# LCDTFT_FPC40P_SPI4_3_2INCH_RTP.net
KiCad netlist of a schematic drawn in Altium Designer
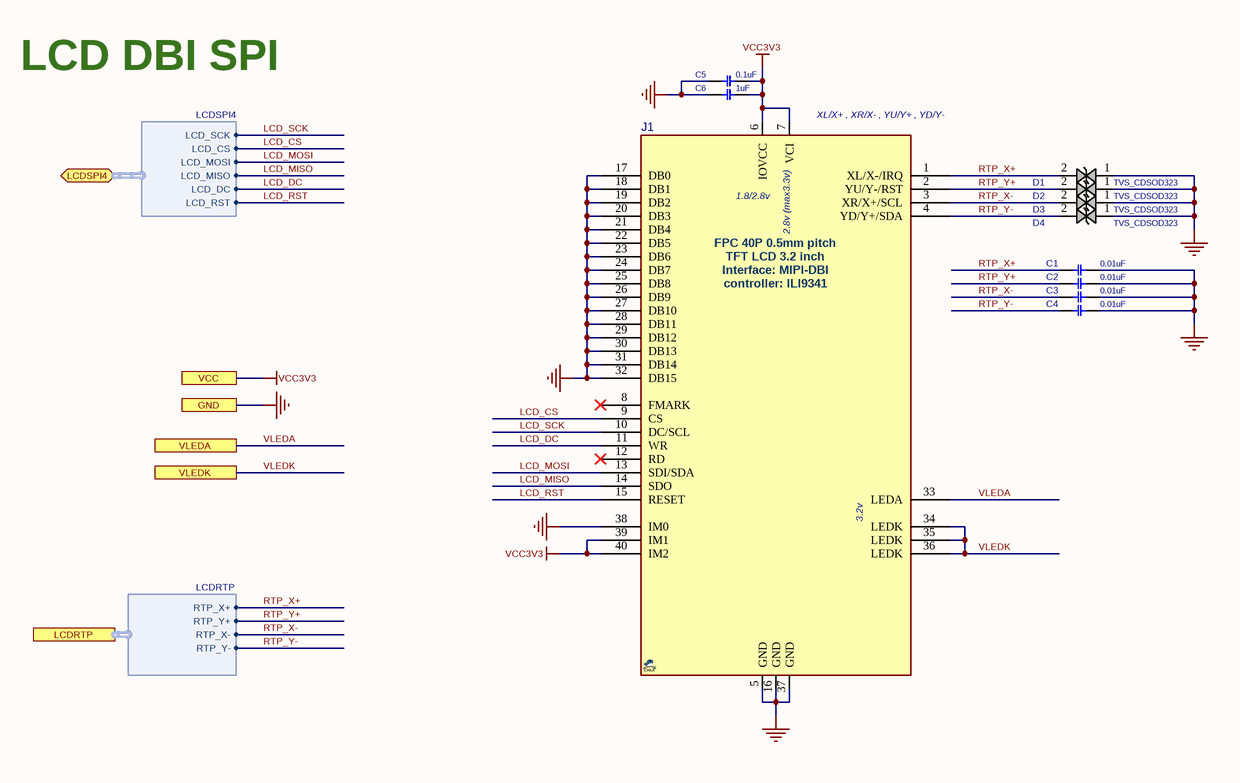
[diagram p0: LCDTFT_FPC40P_SPI4_3.2INCH_RTP.SchDoc]

(export (version "E")
  (design (tool "Eeschema 10.0.6"))
  (components
    (comp (ref "C1")
      (value "0.01uF")
      (footprint "C0402")
      (description "CAP, MLCC")
      (libsource (lib "passive_smd") (part "CAP_SMD_MLCC"))
    )
    (comp (ref "C2")
      (value "0.01uF")
      (footprint "C0402")
      (description "CAP, MLCC")
      (libsource (lib "passive_smd") (part "CAP_SMD_MLCC"))
    )
    (comp (ref "C3")
      (value "0.01uF")
      (footprint "C0402")
      (description "CAP, MLCC")
      (libsource (lib "passive_smd") (part "CAP_SMD_MLCC"))
    )
    (comp (ref "C4")
      (value "0.01uF")
      (footprint "C0402")
      (description "CAP, MLCC")
      (libsource (lib "passive_smd") (part "CAP_SMD_MLCC"))
    )
    (comp (ref "C5")
      (value "0.1uF")
      (footprint "C0402")
      (description "CAP, MLCC")
      (fields (field (name "MANF_P#") "GRM155R71H104KE14D") (field (name "MANF") "Murata"))
      (libsource (lib "passive_smd") (part "CAP_SMD_MLCC"))
    )
    (comp (ref "C6")
      (value "1uF")
      (footprint "C0402")
      (description "CAP, MLCC")
      (libsource (lib "passive_smd") (part "CAP_SMD_MLCC"))
    )
    (comp (ref "D1")
      (value "TVS_CDSOD323")
      (footprint "D0805")
      (description "TVS, ESD PROTECT, Bidirectional")
      (fields (field (name "MANF_P#") "CDSOD323-T12C") (field (name "MANF") "Bourns"))
      (libsource (lib "protect_tvs_esd_fuse") (part "TVS_CDSOD323"))
    )
    (comp (ref "D2")
      (value "TVS_CDSOD323")
      (footprint "D0805")
      (description "TVS, ESD PROTECT, Bidirectional")
      (fields (field (name "MANF_P#") "CDSOD323-T12C") (field (name "MANF") "Bourns"))
      (libsource (lib "protect_tvs_esd_fuse") (part "TVS_CDSOD323"))
    )
    (comp (ref "D3")
      (value "TVS_CDSOD323")
      (footprint "D0805")
      (description "TVS, ESD PROTECT, Bidirectional")
      (fields (field (name "MANF_P#") "CDSOD323-T12C") (field (name "MANF") "Bourns"))
      (libsource (lib "protect_tvs_esd_fuse") (part "TVS_CDSOD323"))
    )
    (comp (ref "D4")
      (value "TVS_CDSOD323")
      (footprint "D0805")
      (description "TVS, ESD PROTECT, Bidirectional")
      (fields (field (name "MANF_P#") "CDSOD323-T12C") (field (name "MANF") "Bourns"))
      (libsource (lib "protect_tvs_esd_fuse") (part "TVS_CDSOD323"))
    )
    (comp (ref "J1")
      (value "FPC50_40")
      (footprint "FPC50_40T")
      (description "LCD TFT Color, FPC40P, 3.2\" with touch")
      (fields (field (name "MANF") "Hirose") (field (name "MANF_P#") "FH12A-40S-0.5SH"))
      (libsource (lib "lcdtft") (part "LCDTFT_DBI_FPC40P_3.2INCH"))
    )
  )
  (nets
    (net (code "3") (name "/LCD_CS") (class "Default")
      (node (ref "J1") (pin "9") (pinfunction "CS_9") (pintype "passive"))
    )
    (net (code "4") (name "/LCD_DC") (class "Default")
      (node (ref "J1") (pin "11") (pinfunction "WR_11") (pintype "passive"))
    )
    (net (code "5") (name "/LCD_MISO") (class "Default")
      (node (ref "J1") (pin "14") (pinfunction "SDO_14") (pintype "passive"))
    )
    (net (code "6") (name "/LCD_MOSI") (class "Default")
      (node (ref "J1") (pin "13") (pinfunction "SDI/SDA_13") (pintype "passive"))
    )
    (net (code "7") (name "/LCD_RST") (class "Default")
      (node (ref "J1") (pin "15") (pinfunction "RESET_15") (pintype "passive"))
    )
    (net (code "8") (name "/LCD_SCK") (class "Default")
      (node (ref "J1") (pin "10") (pinfunction "DC/SCL_10") (pintype "passive"))
    )
    (net (code "9") (name "/RTP_X+") (class "Default")
      (node (ref "C1") (pin "2") (pinfunction "2_2") (pintype "passive"))
      (node (ref "D1") (pin "2") (pinfunction "2_2") (pintype "passive"))
      (node (ref "J1") (pin "1") (pinfunction "XL/X-/IRQ_1") (pintype "passive"))
    )
    (net (code "10") (name "/RTP_X-") (class "Default")
      (node (ref "C3") (pin "2") (pinfunction "2_2") (pintype "passive"))
      (node (ref "D3") (pin "2") (pinfunction "2_2") (pintype "passive"))
      (node (ref "J1") (pin "3") (pinfunction "XR/X+/SCL_3") (pintype "passive"))
    )
    (net (code "11") (name "/RTP_Y+") (class "Default")
      (node (ref "C2") (pin "2") (pinfunction "2_2") (pintype "passive"))
      (node (ref "D2") (pin "2") (pinfunction "2_2") (pintype "passive"))
      (node (ref "J1") (pin "2") (pinfunction "YU/Y-/RST_2") (pintype "passive"))
    )
    (net (code "12") (name "/RTP_Y-") (class "Default")
      (node (ref "C4") (pin "2") (pinfunction "2_2") (pintype "passive"))
      (node (ref "D4") (pin "2") (pinfunction "2_2") (pintype "passive"))
      (node (ref "J1") (pin "4") (pinfunction "YD/Y+/SDA_4") (pintype "passive"))
    )
    (net (code "13") (name "/VLEDA") (class "Default")
      (node (ref "J1") (pin "33") (pinfunction "LEDA_33") (pintype "passive"))
    )
    (net (code "14") (name "/VLEDK") (class "Default")
      (node (ref "J1") (pin "34") (pinfunction "LEDK_34") (pintype "passive"))
      (node (ref "J1") (pin "35") (pinfunction "LEDK_35") (pintype "passive"))
      (node (ref "J1") (pin "36") (pinfunction "LEDK_36") (pintype "passive"))
    )
    (net (code "17") (name "GND") (class "Default")
      (node (ref "C1") (pin "1") (pinfunction "1_1") (pintype "passive"))
      (node (ref "C2") (pin "1") (pinfunction "1_1") (pintype "passive"))
      (node (ref "C3") (pin "1") (pinfunction "1_1") (pintype "passive"))
      (node (ref "C4") (pin "1") (pinfunction "1_1") (pintype "passive"))
      (node (ref "C5") (pin "2") (pinfunction "2_2") (pintype "passive"))
      (node (ref "C6") (pin "2") (pinfunction "2_2") (pintype "passive"))
      (node (ref "D1") (pin "1") (pinfunction "1_1") (pintype "passive"))
      (node (ref "D2") (pin "1") (pinfunction "1_1") (pintype "passive"))
      (node (ref "D3") (pin "1") (pinfunction "1_1") (pintype "passive"))
      (node (ref "D4") (pin "1") (pinfunction "1_1") (pintype "passive"))
      (node (ref "J1") (pin "16") (pinfunction "GND_16") (pintype "passive"))
      (node (ref "J1") (pin "17") (pinfunction "DB0_17") (pintype "passive"))
      (node (ref "J1") (pin "18") (pinfunction "DB1_18") (pintype "passive"))
      (node (ref "J1") (pin "19") (pinfunction "DB2_19") (pintype "passive"))
      (node (ref "J1") (pin "20") (pinfunction "DB3_20") (pintype "passive"))
      (node (ref "J1") (pin "21") (pinfunction "DB4_21") (pintype "passive"))
      (node (ref "J1") (pin "22") (pinfunction "DB5_22") (pintype "passive"))
      (node (ref "J1") (pin "23") (pinfunction "DB6_23") (pintype "passive"))
      (node (ref "J1") (pin "24") (pinfunction "DB7_24") (pintype "passive"))
      (node (ref "J1") (pin "25") (pinfunction "DB8_25") (pintype "passive"))
      (node (ref "J1") (pin "26") (pinfunction "DB9_26") (pintype "passive"))
      (node (ref "J1") (pin "27") (pinfunction "DB10_27") (pintype "passive"))
      (node (ref "J1") (pin "28") (pinfunction "DB11_28") (pintype "passive"))
      (node (ref "J1") (pin "29") (pinfunction "DB12_29") (pintype "passive"))
      (node (ref "J1") (pin "30") (pinfunction "DB13_30") (pintype "passive"))
      (node (ref "J1") (pin "31") (pinfunction "DB14_31") (pintype "passive"))
      (node (ref "J1") (pin "32") (pinfunction "DB15_32") (pintype "passive"))
      (node (ref "J1") (pin "37") (pinfunction "GND_37") (pintype "passive"))
      (node (ref "J1") (pin "38") (pinfunction "IM0_38") (pintype "passive"))
      (node (ref "J1") (pin "5") (pinfunction "GND_5") (pintype "passive"))
    )
    (net (code "18") (name "VCC3V3") (class "Default")
      (node (ref "C5") (pin "1") (pinfunction "1_1") (pintype "passive"))
      (node (ref "C6") (pin "1") (pinfunction "1_1") (pintype "passive"))
      (node (ref "J1") (pin "39") (pinfunction "IM1_39") (pintype "passive"))
      (node (ref "J1") (pin "40") (pinfunction "IM2_40") (pintype "passive"))
      (node (ref "J1") (pin "6") (pinfunction "IOVCC_6") (pintype "passive"))
      (node (ref "J1") (pin "7") (pinfunction "VCI_7") (pintype "passive"))
    )
    (net (code "19") (name "unconnected-(J1-FMARK-Pad8)") (class "Default")
      (node (ref "J1") (pin "8") (pinfunction "FMARK_8") (pintype "passive+no_connect"))
    )
    (net (code "20") (name "unconnected-(J1-RD-Pad12)") (class "Default")
      (node (ref "J1") (pin "12") (pinfunction "RD_12") (pintype "passive+no_connect"))
    )
  )
)
